# Sheet2.net
KiCad netlist of a schematic drawn in Altium Designer
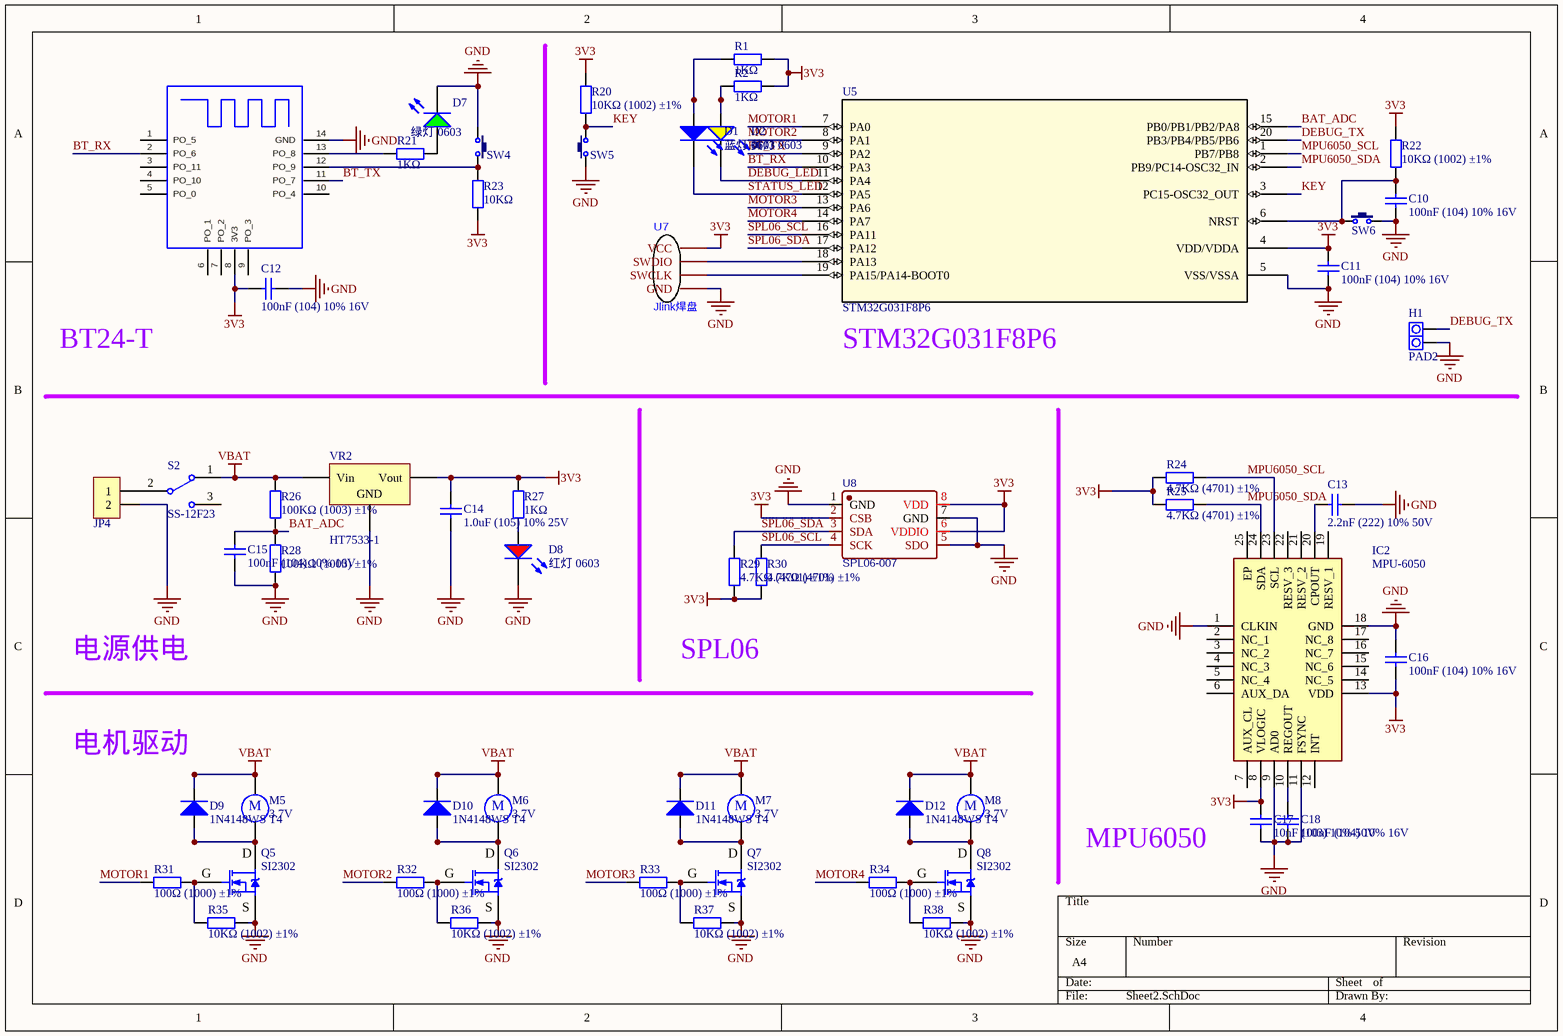
[diagram p0: Sheet2.SchDoc]

(export (version "E")
  (design (tool "Eeschema 10.0.6"))
  (components
    (comp (ref "C10")
      (value "100nF (104) 10% 16V")
      (footprint "0402_C")
      (description "贴片电容")
      (libsource (lib "Cap") (part "0402 100nF (104) 10% 16V"))
    )
    (comp (ref "C11")
      (value "100nF (104) 10% 16V")
      (footprint "0402_C")
      (description "贴片电容")
      (libsource (lib "Cap") (part "0402 100nF (104) 10% 16V"))
    )
    (comp (ref "C12")
      (value "100nF (104) 10% 16V")
      (footprint "0402_C")
      (description "贴片电容")
      (libsource (lib "Cap") (part "0402 100nF (104) 10% 16V"))
    )
    (comp (ref "C13")
      (value "2.2nF (222) 10% 50V")
      (footprint "0402_C")
      (description "贴片电容")
      (libsource (lib "Cap") (part "0402 2.2nF (222) 10% 50V"))
    )
    (comp (ref "C14")
      (value "1.0uF (105) 10% 25V")
      (footprint "0402_C")
      (description "贴片电容")
      (libsource (lib "Cap") (part "0402 1.0uF (105) 10% 25V"))
    )
    (comp (ref "C15")
      (value "100nF (104) 10% 16V")
      (footprint "0402_C")
      (description "贴片电容")
      (libsource (lib "Cap") (part "0402 100nF (104) 10% 16V"))
    )
    (comp (ref "C16")
      (value "100nF (104) 10% 16V")
      (footprint "0402_C")
      (description "贴片电容")
      (libsource (lib "Cap") (part "0402 100nF (104) 10% 16V"))
    )
    (comp (ref "C17")
      (value "10nF (103) 10% 50V")
      (footprint "0402_C")
      (description "贴片电容")
      (libsource (lib "Cap") (part "0402 10nF (103) 10% 50V"))
    )
    (comp (ref "C18")
      (value "100nF (104) 10% 16V")
      (footprint "0402_C")
      (description "贴片电容")
      (libsource (lib "Cap") (part "0402 100nF (104) 10% 16V"))
    )
    (comp (ref "D1")
      (value "蓝灯 0603")
      (footprint "0603_LED_S1")
      (description "发光二极管")
      (libsource (lib "LED") (part "0603 蓝灯"))
    )
    (comp (ref "D2")
      (value "黄灯 0603")
      (footprint "0603_LED_S1")
      (description "发光二极管")
      (libsource (lib "LED") (part "0603 黄灯"))
    )
    (comp (ref "D7")
      (value "绿灯 0603")
      (footprint "0603_LED_S1")
      (description "发光二极管")
      (libsource (lib "LED") (part "0603 绿灯"))
    )
    (comp (ref "D8")
      (value "红灯 0603")
      (footprint "0603_LED_S1")
      (description "发光二极管")
      (libsource (lib "LED") (part "0603 红灯"))
    )
    (comp (ref "D9")
      (value "1N4148WS T4")
      (footprint "SOD-323")
      (description "二极管")
      (libsource (lib "Diode") (part "SOD-323 1N4148WS T4"))
    )
    (comp (ref "D10")
      (value "1N4148WS T4")
      (footprint "SOD-323")
      (description "二极管")
      (libsource (lib "Diode") (part "SOD-323 1N4148WS T4"))
    )
    (comp (ref "D11")
      (value "1N4148WS T4")
      (footprint "SOD-323")
      (description "二极管")
      (libsource (lib "Diode") (part "SOD-323 1N4148WS T4"))
    )
    (comp (ref "D12")
      (value "1N4148WS T4")
      (footprint "SOD-323")
      (description "二极管")
      (libsource (lib "Diode") (part "SOD-323 1N4148WS T4"))
    )
    (comp (ref "H1")
      (value "PAD2")
      (footprint "PAD2-2.54")
      (description "引线焊盘")
      (fields (field (name "版权归属") "源创客"))
      (libsource (lib "15.1 - 未分类器件") (part "PAD2"))
    )
    (comp (ref "IC2")
      (value "MPU-6050")
      (footprint "SamacSys:MPU6050")
      (description "Integrated Circuit")
      (fields (field (name "MOUSER PART NUMBER") "410-MPU-6050"))
      (libsource (lib "*") (part "MPU-6050"))
    )
    (comp (ref "JP4")
      (value "HDR-1X2")
      (footprint "ZH1.5-WI-2P")
      (description "2P接插件")
      (fields (field (name "版权归属") "源创客"))
      (libsource (lib "4.3   - 接插件-脚距1.5") (part "Header 2"))
    )
    (comp (ref "M5")
      (value "3.7V")
      (footprint "MX 1.25-WI-2P")
      (description "直流电机")
      (fields (field (name "版权归属") "源创客"))
      (libsource (lib "15.1 - 未分类器件") (part "MOTOR"))
    )
    (comp (ref "M6")
      (value "3.7V")
      (footprint "MX 1.25-WI-2P")
      (description "直流电机")
      (fields (field (name "版权归属") "源创客"))
      (libsource (lib "15.1 - 未分类器件") (part "MOTOR"))
    )
    (comp (ref "M7")
      (value "3.7V")
      (footprint "MX 1.25-WI-2P")
      (description "直流电机")
      (fields (field (name "版权归属") "源创客"))
      (libsource (lib "15.1 - 未分类器件") (part "MOTOR"))
    )
    (comp (ref "M8")
      (value "3.7V")
      (footprint "MX 1.25-WI-2P")
      (description "直流电机")
      (fields (field (name "版权归属") "源创客"))
      (libsource (lib "15.1 - 未分类器件") (part "MOTOR"))
    )
    (comp (ref "Q5")
      (value "SI2302")
      (footprint "SOT23-3N")
      (description "N沟道场效应管")
      (fields (field (name "版权归属") "源创客"))
      (libsource (lib "6.1   - 场效应管-可控硅") (part "SI2302"))
    )
    (comp (ref "Q6")
      (value "SI2302")
      (footprint "SOT23-3N")
      (description "N沟道场效应管")
      (fields (field (name "版权归属") "源创客"))
      (libsource (lib "6.1   - 场效应管-可控硅") (part "SI2302"))
    )
    (comp (ref "Q7")
      (value "SI2302")
      (footprint "SOT23-3N")
      (description "N沟道场效应管")
      (fields (field (name "版权归属") "源创客"))
      (libsource (lib "6.1   - 场效应管-可控硅") (part "SI2302"))
    )
    (comp (ref "Q8")
      (value "SI2302")
      (footprint "SOT23-3N")
      (description "N沟道场效应管")
      (fields (field (name "版权归属") "源创客"))
      (libsource (lib "6.1   - 场效应管-可控硅") (part "SI2302"))
    )
    (comp (ref "R1")
      (value "1KΩ")
      (footprint "0402_R")
      (description "贴片电阻")
      (libsource (lib "RES") (part "0402 1KΩ (1001) 1%"))
    )
    (comp (ref "R2")
      (value "1KΩ")
      (footprint "0402_R")
      (description "贴片电阻")
      (libsource (lib "") (part "0402 1KΩ (1001) 1%_1"))
    )
    (comp (ref "R20")
      (value "10KΩ (1002) ±1%")
      (footprint "0402_R")
      (description "贴片电阻")
      (libsource (lib "") (part "0402 10KΩ (1002) 1%_2"))
    )
    (comp (ref "R21")
      (value "1KΩ")
      (footprint "0402_R")
      (description "贴片电阻")
      (libsource (lib "RES") (part "0402 1KΩ (1001) 1%"))
    )
    (comp (ref "R22")
      (value "10KΩ (1002) ±1%")
      (footprint "0402_R")
      (description "贴片电阻")
      (libsource (lib "") (part "0402 10KΩ (1002) 1%_1"))
    )
    (comp (ref "R23")
      (value "10KΩ")
      (footprint "0402_R")
      (description "贴片电阻")
      (libsource (lib "") (part "0402 10KΩ (1002) 1%_1"))
    )
    (comp (ref "R24")
      (value "4.7KΩ (4701) ±1%")
      (footprint "0402_R")
      (description "贴片电阻")
      (libsource (lib "") (part "0402 4.7KΩ (4701) 1%_1"))
    )
    (comp (ref "R25")
      (value "4.7KΩ (4701) ±1%")
      (footprint "0402_R")
      (description "贴片电阻")
      (libsource (lib "") (part "0402 4.7KΩ (4701) 1%_1"))
    )
    (comp (ref "R26")
      (value "100KΩ (1003) ±1%")
      (footprint "0402_R")
      (description "贴片电阻")
      (libsource (lib "RES") (part "0402 100KΩ (1003) 1%"))
    )
    (comp (ref "R27")
      (value "1KΩ")
      (footprint "0402_R")
      (description "贴片电阻")
      (libsource (lib "") (part "0402 1KΩ (1001) 1%_2"))
    )
    (comp (ref "R28")
      (value "100KΩ (1003) ±1%")
      (footprint "0402_R")
      (description "贴片电阻")
      (libsource (lib "RES") (part "0402 100KΩ (1003) 1%"))
    )
    (comp (ref "R29")
      (value "4.7KΩ (4701) ±1%")
      (footprint "0402_R")
      (description "贴片电阻")
      (libsource (lib "RES") (part "0402 4.7KΩ (4701) 1%"))
    )
    (comp (ref "R30")
      (value "4.7KΩ (4701) ±1%")
      (footprint "0402_R")
      (description "贴片电阻")
      (libsource (lib "RES") (part "0402 4.7KΩ (4701) 1%"))
    )
    (comp (ref "R31")
      (value "100Ω (1000) ±1%")
      (footprint "0402_R")
      (description "贴片电阻")
      (libsource (lib "RES") (part "0402 100Ω (1000) 1%"))
    )
    (comp (ref "R32")
      (value "100Ω (1000) ±1%")
      (footprint "0402_R")
      (description "贴片电阻")
      (libsource (lib "RES") (part "0402 100Ω (1000) 1%"))
    )
    (comp (ref "R33")
      (value "100Ω (1000) ±1%")
      (footprint "0402_R")
      (description "贴片电阻")
      (libsource (lib "RES") (part "0402 100Ω (1000) 1%"))
    )
    (comp (ref "R34")
      (value "100Ω (1000) ±1%")
      (footprint "0402_R")
      (description "贴片电阻")
      (libsource (lib "RES") (part "0402 100Ω (1000) 1%"))
    )
    (comp (ref "R35")
      (value "10KΩ (1002) ±1%")
      (footprint "0402_R")
      (description "贴片电阻")
      (libsource (lib "RES") (part "0402 10KΩ (1002) 1%"))
    )
    (comp (ref "R36")
      (value "10KΩ (1002) ±1%")
      (footprint "0402_R")
      (description "贴片电阻")
      (libsource (lib "RES") (part "0402 10KΩ (1002) 1%"))
    )
    (comp (ref "R37")
      (value "10KΩ (1002) ±1%")
      (footprint "0402_R")
      (description "贴片电阻")
      (libsource (lib "RES") (part "0402 10KΩ (1002) 1%"))
    )
    (comp (ref "R38")
      (value "10KΩ (1002) ±1%")
      (footprint "0402_R")
      (description "贴片电阻")
      (libsource (lib "RES") (part "0402 10KΩ (1002) 1%"))
    )
    (comp (ref "S2")
      (value "SS-12F23")
      (footprint "MSK-12C01-07")
      (description "1路波动开关")
      (fields (field (name "版权归属") "源创客"))
      (libsource (lib "5.1   - 按键-开关") (part "SSW-1P"))
    )
    (comp (ref "SW4")
      (value "3x6x5")
      (footprint "SW-SMD_4P-L5.1-W5.1-P3.70-LS6.5-TL-2")
      (description "3x6轻触开关")
      (fields (field (name "版权归属") "源创客"))
      (libsource (lib "5.1   - 按键-开关") (part "TSW 3x6"))
    )
    (comp (ref "SW5")
      (value "3x6x5")
      (footprint "SW-SMD_4P-L5.1-W5.1-P3.70-LS6.5-TL-2")
      (description "3x6轻触开关")
      (fields (field (name "版权归属") "源创客"))
      (libsource (lib "") (part "TSW 3x6_1"))
    )
    (comp (ref "SW6")
      (value "3x6x5")
      (footprint "SW-SMD_4P-L5.1-W5.1-P3.70-LS6.5-TL-2")
      (description "3x6轻触开关")
      (fields (field (name "版权归属") "源创客"))
      (libsource (lib "") (part "TSW 3x6_2"))
    )
    (comp (ref "U5")
      (value "STM32G031F8P6")
      (footprint "TSSOP20")
      (description "No Description Available")
      (fields (field (name "COPYRIGHT") "Copyright (C) 2022 Ultra Librarian. All rights reserved."))
      (libsource (lib "STM32G031F8P6") (part "STM32G031F8P6"))
    )
    (comp (ref "U6") (value "BT24T") (footprint "CC2640T") (libsource (lib "BT24-T") (part "BT24T")))
    (comp (ref "U7")
      (value "Jlink焊盘")
      (footprint "jlink焊盘:PCBComponent_1 - duplicate")
      (libsource (lib "jlink焊盘") (part "Jlink焊盘"))
    )
    (comp (ref "U8")
      (value "SPL06-007")
      (footprint "SENSOR-SMD_SPL06-007")
      (fields (field (name "BOM_SUPPLIER PART") "C233787") (field (name "CONTRIBUTOR") "LCSC"))
      (libsource (lib "SPL06") (part "SPL06-007"))
    )
    (comp (ref "VR2")
      (value "HT7533-1")
      (footprint "SOT-89(SOT-89-3)")
      (description "低压差线性稳压(LDO)")
      (libsource (lib "LDO") (part "SOT-89 HT7533-1"))
    )
  )
  (nets
    (net (code "1") (name "/BAT_ADC") (class "Default")
      (node (ref "C15") (pin "2") (pinfunction "2_2") (pintype "passive"))
      (node (ref "R26") (pin "1") (pinfunction "1_1") (pintype "passive"))
      (node (ref "R28") (pin "2") (pinfunction "2_2") (pintype "passive"))
      (node (ref "U5") (pin "15") (pinfunction "PB0/PB1/PB2/PA8_15") (pintype "bidirectional"))
    )
    (net (code "2") (name "/BT_RX") (class "Default")
      (node (ref "U5") (pin "10") (pinfunction "PA3_10") (pintype "bidirectional"))
      (node (ref "U6") (pin "2") (pinfunction "PO_6_2") (pintype "passive"))
    )
    (net (code "3") (name "/BT_TX") (class "Default")
      (node (ref "U5") (pin "9") (pinfunction "PA2_9") (pintype "bidirectional"))
      (node (ref "U6") (pin "11") (pinfunction "PO_7_11") (pintype "passive"))
    )
    (net (code "4") (name "/DEBUG_LED") (class "Default")
      (node (ref "D2") (pin "K") (pinfunction "K_K") (pintype "passive"))
      (node (ref "U5") (pin "11") (pinfunction "PA4_11") (pintype "bidirectional"))
    )
    (net (code "5") (name "/DEBUG_TX") (class "Default")
      (node (ref "H1") (pin "2") (pinfunction "2_2") (pintype "passive"))
      (node (ref "U5") (pin "20") (pinfunction "PB3/PB4/PB5/PB6_20") (pintype "bidirectional"))
    )
    (net (code "6") (name "/KEY") (class "Default")
      (node (ref "R20") (pin "1") (pinfunction "1_1") (pintype "passive"))
      (node (ref "SW5") (pin "2") (pinfunction "2_2") (pintype "passive"))
      (node (ref "U5") (pin "3") (pinfunction "PC15-OSC32_OUT_3") (pintype "bidirectional"))
    )
    (net (code "7") (name "/MOTOR1") (class "Default")
      (node (ref "R31") (pin "1") (pinfunction "1_1") (pintype "passive"))
      (node (ref "U5") (pin "7") (pinfunction "PA0_7") (pintype "bidirectional"))
    )
    (net (code "8") (name "/MOTOR2") (class "Default")
      (node (ref "R32") (pin "1") (pinfunction "1_1") (pintype "passive"))
      (node (ref "U5") (pin "8") (pinfunction "PA1_8") (pintype "bidirectional"))
    )
    (net (code "9") (name "/MOTOR3") (class "Default")
      (node (ref "R33") (pin "1") (pinfunction "1_1") (pintype "passive"))
      (node (ref "U5") (pin "13") (pinfunction "PA6_13") (pintype "bidirectional"))
    )
    (net (code "10") (name "/MOTOR4") (class "Default")
      (node (ref "R34") (pin "1") (pinfunction "1_1") (pintype "passive"))
      (node (ref "U5") (pin "14") (pinfunction "PA7_14") (pintype "bidirectional"))
    )
    (net (code "11") (name "/MPU6050_SCL") (class "Default")
      (node (ref "IC2") (pin "23") (pinfunction "SCL_23") (pintype "passive"))
      (node (ref "R24") (pin "2") (pinfunction "2_2") (pintype "passive"))
      (node (ref "U5") (pin "1") (pinfunction "PB7/PB8_1") (pintype "bidirectional"))
    )
    (net (code "12") (name "/MPU6050_SDA") (class "Default")
      (node (ref "IC2") (pin "24") (pinfunction "SDA_24") (pintype "passive"))
      (node (ref "R25") (pin "2") (pinfunction "2_2") (pintype "passive"))
      (node (ref "U5") (pin "2") (pinfunction "PB9/PC14-OSC32_IN_2") (pintype "bidirectional"))
    )
    (net (code "13") (name "/SPL06_SCL") (class "Default")
      (node (ref "R30") (pin "2") (pinfunction "2_2") (pintype "passive"))
      (node (ref "U5") (pin "16") (pinfunction "PA11_16") (pintype "bidirectional"))
      (node (ref "U8") (pin "4") (pinfunction "SCK_4") (pintype "passive"))
    )
    (net (code "14") (name "/SPL06_SDA") (class "Default")
      (node (ref "R29") (pin "2") (pinfunction "2_2") (pintype "passive"))
      (node (ref "U5") (pin "17") (pinfunction "PA12_17") (pintype "bidirectional"))
      (node (ref "U8") (pin "3") (pinfunction "SDA_3") (pintype "passive"))
    )
    (net (code "15") (name "/STATUS_LED") (class "Default")
      (node (ref "D1") (pin "K") (pinfunction "K_K") (pintype "passive"))
      (node (ref "U5") (pin "12") (pinfunction "PA5_12") (pintype "bidirectional"))
    )
    (net (code "16") (name "3V3") (class "Default")
      (node (ref "C11") (pin "1") (pinfunction "1_1") (pintype "passive"))
      (node (ref "C12") (pin "2") (pinfunction "2_2") (pintype "passive"))
      (node (ref "C14") (pin "2") (pinfunction "2_2") (pintype "passive"))
      (node (ref "C16") (pin "1") (pinfunction "1_1") (pintype "passive"))
      (node (ref "C17") (pin "2") (pinfunction "2_2") (pintype "passive"))
      (node (ref "IC2") (pin "13") (pinfunction "VDD_13") (pintype "passive"))
      (node (ref "IC2") (pin "8") (pinfunction "VLOGIC_8") (pintype "passive"))
      (node (ref "R1") (pin "2") (pinfunction "2_2") (pintype "passive"))
      (node (ref "R2") (pin "1") (pinfunction "1_1") (pintype "passive"))
      (node (ref "R20") (pin "2") (pinfunction "2_2") (pintype "passive"))
      (node (ref "R22") (pin "1") (pinfunction "1_1") (pintype "passive"))
      (node (ref "R23") (pin "2") (pinfunction "2_2") (pintype "passive"))
      (node (ref "R24") (pin "1") (pinfunction "1_1") (pintype "passive"))
      (node (ref "R25") (pin "1") (pinfunction "1_1") (pintype "passive"))
      (node (ref "R27") (pin "2") (pinfunction "2_2") (pintype "passive"))
      (node (ref "R29") (pin "1") (pinfunction "1_1") (pintype "passive"))
      (node (ref "R30") (pin "1") (pinfunction "1_1") (pintype "passive"))
      (node (ref "U5") (pin "4") (pinfunction "VDD/VDDA_4") (pintype "power_in"))
      (node (ref "U6") (pin "8") (pinfunction "3V3_8") (pintype "passive"))
      (node (ref "U7") (pin "1") (pinfunction "VCC_1") (pintype "passive"))
      (node (ref "U8") (pin "2") (pinfunction "CSB_2") (pintype "passive"))
      (node (ref "U8") (pin "6") (pinfunction "VDDIO_6") (pintype "passive"))
      (node (ref "U8") (pin "8") (pinfunction "VDD_8") (pintype "passive"))
      (node (ref "VR2") (pin "3") (pinfunction "Vout_3") (pintype "passive"))
    )
    (net (code "17") (name "GND") (class "Default")
      (node (ref "C10") (pin "2") (pinfunction "2_2") (pintype "passive"))
      (node (ref "C11") (pin "2") (pinfunction "2_2") (pintype "passive"))
      (node (ref "C12") (pin "1") (pinfunction "1_1") (pintype "passive"))
      (node (ref "C13") (pin "2") (pinfunction "2_2") (pintype "passive"))
      (node (ref "C14") (pin "1") (pinfunction "1_1") (pintype "passive"))
      (node (ref "C15") (pin "1") (pinfunction "1_1") (pintype "passive"))
      (node (ref "C16") (pin "2") (pinfunction "2_2") (pintype "passive"))
      (node (ref "C17") (pin "1") (pinfunction "1_1") (pintype "passive"))
      (node (ref "C18") (pin "1") (pinfunction "1_1") (pintype "passive"))
      (node (ref "D7") (pin "K") (pinfunction "K_K") (pintype "passive"))
      (node (ref "D8") (pin "K") (pinfunction "K_K") (pintype "passive"))
      (node (ref "H1") (pin "1") (pinfunction "1_1") (pintype "passive"))
      (node (ref "IC2") (pin "1") (pinfunction "CLKIN_1") (pintype "passive"))
      (node (ref "IC2") (pin "11") (pinfunction "FSYNC_11") (pintype "passive"))
      (node (ref "IC2") (pin "18") (pinfunction "GND_18") (pintype "passive"))
      (node (ref "IC2") (pin "9") (pinfunction "AD0_9") (pintype "passive"))
      (node (ref "JP4") (pin "2") (pinfunction "2_2") (pintype "passive"))
      (node (ref "Q5") (pin "2") (pinfunction "S_2") (pintype "passive"))
      (node (ref "Q6") (pin "2") (pinfunction "S_2") (pintype "passive"))
      (node (ref "Q7") (pin "2") (pinfunction "S_2") (pintype "passive"))
      (node (ref "Q8") (pin "2") (pinfunction "S_2") (pintype "passive"))
      (node (ref "R28") (pin "1") (pinfunction "1_1") (pintype "passive"))
      (node (ref "R35") (pin "2") (pinfunction "2_2") (pintype "passive"))
      (node (ref "R36") (pin "2") (pinfunction "2_2") (pintype "passive"))
      (node (ref "R37") (pin "2") (pinfunction "2_2") (pintype "passive"))
      (node (ref "R38") (pin "2") (pinfunction "2_2") (pintype "passive"))
      (node (ref "SW4") (pin "1") (pinfunction "1_1") (pintype "passive"))
      (node (ref "SW5") (pin "1") (pinfunction "1_1") (pintype "passive"))
      (node (ref "SW6") (pin "2") (pinfunction "2_2") (pintype "passive"))
      (node (ref "U5") (pin "5") (pinfunction "VSS/VSSA_5") (pintype "power_in"))
      (node (ref "U6") (pin "14") (pinfunction "GND_14") (pintype "passive"))
      (node (ref "U7") (pin "4") (pinfunction "GND_4") (pintype "passive"))
      (node (ref "U8") (pin "1") (pinfunction "GND_1") (pintype "passive"))
      (node (ref "U8") (pin "5") (pinfunction "SDO_5") (pintype "passive"))
      (node (ref "U8") (pin "7") (pinfunction "GND_7") (pintype "passive"))
      (node (ref "VR2") (pin "1") (pinfunction "GND_1") (pintype "passive"))
    )
    (net (code "18") (name "Net-(D1-PadA)") (class "Default")
      (node (ref "D1") (pin "A") (pinfunction "A_A") (pintype "passive"))
      (node (ref "R1") (pin "1") (pinfunction "1_1") (pintype "passive"))
    )
    (net (code "19") (name "Net-(D2-PadA)") (class "Default")
      (node (ref "D2") (pin "A") (pinfunction "A_A") (pintype "passive"))
      (node (ref "R2") (pin "2") (pinfunction "2_2") (pintype "passive"))
    )
    (net (code "20") (name "Net-(D7-PadA)") (class "Default")
      (node (ref "D7") (pin "A") (pinfunction "A_A") (pintype "passive"))
      (node (ref "R21") (pin "2") (pinfunction "2_2") (pintype "passive"))
    )
    (net (code "21") (name "Net-(D8-PadA)") (class "Default")
      (node (ref "D8") (pin "A") (pinfunction "A_A") (pintype "passive"))
      (node (ref "R27") (pin "1") (pinfunction "1_1") (pintype "passive"))
    )
    (net (code "22") (name "Net-(D9-A)") (class "Default")
      (node (ref "D9") (pin "1") (pinfunction "A_1") (pintype "passive"))
      (node (ref "M5") (pin "2") (pinfunction "2_2") (pintype "passive"))
      (node (ref "Q5") (pin "3") (pinfunction "D_3") (pintype "passive"))
    )
    (net (code "23") (name "Net-(D10-A)") (class "Default")
      (node (ref "D10") (pin "1") (pinfunction "A_1") (pintype "passive"))
      (node (ref "M6") (pin "2") (pinfunction "2_2") (pintype "passive"))
      (node (ref "Q6") (pin "3") (pinfunction "D_3") (pintype "passive"))
    )
    (net (code "24") (name "Net-(D11-A)") (class "Default")
      (node (ref "D11") (pin "1") (pinfunction "A_1") (pintype "passive"))
      (node (ref "M7") (pin "2") (pinfunction "2_2") (pintype "passive"))
      (node (ref "Q7") (pin "3") (pinfunction "D_3") (pintype "passive"))
    )
    (net (code "25") (name "Net-(D12-A)") (class "Default")
      (node (ref "D12") (pin "1") (pinfunction "A_1") (pintype "passive"))
      (node (ref "M8") (pin "2") (pinfunction "2_2") (pintype "passive"))
      (node (ref "Q8") (pin "3") (pinfunction "D_3") (pintype "passive"))
    )
    (net (code "26") (name "Net-(IC2-CPOUT)") (class "Default")
      (node (ref "C13") (pin "1") (pinfunction "1_1") (pintype "passive"))
      (node (ref "IC2") (pin "20") (pinfunction "CPOUT_20") (pintype "passive"))
    )
    (net (code "27") (name "Net-(IC2-REGOUT)") (class "Default")
      (node (ref "C18") (pin "2") (pinfunction "2_2") (pintype "passive"))
      (node (ref "IC2") (pin "10") (pinfunction "REGOUT_10") (pintype "passive"))
    )
    (net (code "28") (name "Net-(JP4-Pad1)") (class "Default")
      (node (ref "JP4") (pin "1") (pinfunction "1_1") (pintype "passive"))
      (node (ref "S2") (pin "2") (pinfunction "2_2") (pintype "passive"))
    )
    (net (code "29") (name "Net-(Q5-G)") (class "Default")
      (node (ref "Q5") (pin "1") (pinfunction "G_1") (pintype "passive"))
      (node (ref "R31") (pin "2") (pinfunction "2_2") (pintype "passive"))
      (node (ref "R35") (pin "1") (pinfunction "1_1") (pintype "passive"))
    )
    (net (code "30") (name "Net-(Q6-G)") (class "Default")
      (node (ref "Q6") (pin "1") (pinfunction "G_1") (pintype "passive"))
      (node (ref "R32") (pin "2") (pinfunction "2_2") (pintype "passive"))
      (node (ref "R36") (pin "1") (pinfunction "1_1") (pintype "passive"))
    )
    (net (code "31") (name "Net-(Q7-G)") (class "Default")
      (node (ref "Q7") (pin "1") (pinfunction "G_1") (pintype "passive"))
      (node (ref "R33") (pin "2") (pinfunction "2_2") (pintype "passive"))
      (node (ref "R37") (pin "1") (pinfunction "1_1") (pintype "passive"))
    )
    (net (code "32") (name "Net-(Q8-G)") (class "Default")
      (node (ref "Q8") (pin "1") (pinfunction "G_1") (pintype "passive"))
      (node (ref "R34") (pin "2") (pinfunction "2_2") (pintype "passive"))
      (node (ref "R38") (pin "1") (pinfunction "1_1") (pintype "passive"))
    )
    (net (code "33") (name "Net-(U5-NRST)") (class "Default")
      (node (ref "C10") (pin "1") (pinfunction "1_1") (pintype "passive"))
      (node (ref "R22") (pin "2") (pinfunction "2_2") (pintype "passive"))
      (node (ref "SW6") (pin "1") (pinfunction "1_1") (pintype "passive"))
      (node (ref "U5") (pin "6") (pinfunction "NRST_6") (pintype "bidirectional"))
    )
    (net (code "34") (name "Net-(U5-PA13)") (class "Default")
      (node (ref "U5") (pin "18") (pinfunction "PA13_18") (pintype "bidirectional"))
      (node (ref "U7") (pin "2") (pinfunction "SWDIO_2") (pintype "passive"))
    )
    (net (code "35") (name "Net-(U5-PA15{slash}PA14-BOOT0)") (class "Default")
      (node (ref "U5") (pin "19") (pinfunction "PA15/PA14-BOOT0_19") (pintype "bidirectional"))
      (node (ref "U7") (pin "3") (pinfunction "SWCLK_3") (pintype "passive"))
    )
    (net (code "36") (name "Net-(U6-PO_8)") (class "Default")
      (node (ref "R21") (pin "1") (pinfunction "1_1") (pintype "passive"))
      (node (ref "U6") (pin "13") (pinfunction "PO_8_13") (pintype "passive"))
    )
    (net (code "37") (name "Net-(U6-PO_9)") (class "Default")
      (node (ref "R23") (pin "1") (pinfunction "1_1") (pintype "passive"))
      (node (ref "SW4") (pin "2") (pinfunction "2_2") (pintype "passive"))
      (node (ref "U6") (pin "12") (pinfunction "PO_9_12") (pintype "passive"))
    )
    (net (code "38") (name "VBAT") (class "Default")
      (node (ref "D10") (pin "2") (pinfunction "K_2") (pintype "passive"))
      (node (ref "D11") (pin "2") (pinfunction "K_2") (pintype "passive"))
      (node (ref "D12") (pin "2") (pinfunction "K_2") (pintype "passive"))
      (node (ref "D9") (pin "2") (pinfunction "K_2") (pintype "passive"))
      (node (ref "M5") (pin "1") (pinfunction "1_1") (pintype "passive"))
      (node (ref "M6") (pin "1") (pinfunction "1_1") (pintype "passive"))
      (node (ref "M7") (pin "1") (pinfunction "1_1") (pintype "passive"))
      (node (ref "M8") (pin "1") (pinfunction "1_1") (pintype "passive"))
      (node (ref "R26") (pin "2") (pinfunction "2_2") (pintype "passive"))
      (node (ref "S2") (pin "1") (pinfunction "1_1") (pintype "passive"))
      (node (ref "VR2") (pin "2") (pinfunction "Vin_2") (pintype "passive"))
    )
    (net (code "39") (name "unconnected-(IC2-AUX_CL-Pad7)") (class "Default")
      (node (ref "IC2") (pin "7") (pinfunction "AUX_CL_7") (pintype "passive"))
    )
    (net (code "40") (name "unconnected-(IC2-AUX_DA-Pad6)") (class "Default")
      (node (ref "IC2") (pin "6") (pinfunction "AUX_DA_6") (pintype "passive"))
    )
    (net (code "41") (name "unconnected-(IC2-EP-Pad25)") (class "Default")
      (node (ref "IC2") (pin "25") (pinfunction "EP_25") (pintype "passive"))
    )
    (net (code "42") (name "unconnected-(IC2-INT-Pad12)") (class "Default")
      (node (ref "IC2") (pin "12") (pinfunction "INT_12") (pintype "passive"))
    )
    (net (code "43") (name "unconnected-(IC2-NC_1-Pad2)") (class "Default")
      (node (ref "IC2") (pin "2") (pinfunction "NC_1_2") (pintype "passive"))
    )
    (net (code "44") (name "unconnected-(IC2-NC_2-Pad3)") (class "Default")
      (node (ref "IC2") (pin "3") (pinfunction "NC_2_3") (pintype "passive"))
    )
    (net (code "45") (name "unconnected-(IC2-NC_3-Pad4)") (class "Default")
      (node (ref "IC2") (pin "4") (pinfunction "NC_3_4") (pintype "passive"))
    )
    (net (code "46") (name "unconnected-(IC2-NC_4-Pad5)") (class "Default")
      (node (ref "IC2") (pin "5") (pinfunction "NC_4_5") (pintype "passive"))
    )
    (net (code "47") (name "unconnected-(IC2-NC_5-Pad14)") (class "Default")
      (node (ref "IC2") (pin "14") (pinfunction "NC_5_14") (pintype "passive"))
    )
    (net (code "48") (name "unconnected-(IC2-NC_6-Pad15)") (class "Default")
      (node (ref "IC2") (pin "15") (pinfunction "NC_6_15") (pintype "passive"))
    )
    (net (code "49") (name "unconnected-(IC2-NC_7-Pad16)") (class "Default")
      (node (ref "IC2") (pin "16") (pinfunction "NC_7_16") (pintype "passive"))
    )
    (net (code "50") (name "unconnected-(IC2-NC_8-Pad17)") (class "Default")
      (node (ref "IC2") (pin "17") (pinfunction "NC_8_17") (pintype "passive"))
    )
    (net (code "51") (name "unconnected-(IC2-RESV_1-Pad19)") (class "Default")
      (node (ref "IC2") (pin "19") (pinfunction "RESV_1_19") (pintype "passive"))
    )
    (net (code "52") (name "unconnected-(IC2-RESV_2-Pad21)") (class "Default")
      (node (ref "IC2") (pin "21") (pinfunction "RESV_2_21") (pintype "passive"))
    )
    (net (code "53") (name "unconnected-(IC2-RESV_3-Pad22)") (class "Default")
      (node (ref "IC2") (pin "22") (pinfunction "RESV_3_22") (pintype "passive"))
    )
    (net (code "54") (name "unconnected-(S2-Pad3)") (class "Default")
      (node (ref "S2") (pin "3") (pinfunction "3_3") (pintype "passive"))
    )
    (net (code "55") (name "unconnected-(U6-PO_0-Pad5)") (class "Default")
      (node (ref "U6") (pin "5") (pinfunction "PO_0_5") (pintype "passive"))
    )
    (net (code "56") (name "unconnected-(U6-PO_1-Pad6)") (class "Default")
      (node (ref "U6") (pin "6") (pinfunction "PO_1_6") (pintype "passive"))
    )
    (net (code "57") (name "unconnected-(U6-PO_2-Pad7)") (class "Default")
      (node (ref "U6") (pin "7") (pinfunction "PO_2_7") (pintype "passive"))
    )
    (net (code "58") (name "unconnected-(U6-PO_3-Pad9)") (class "Default")
      (node (ref "U6") (pin "9") (pinfunction "PO_3_9") (pintype "passive"))
    )
    (net (code "59") (name "unconnected-(U6-PO_4-Pad10)") (class "Default")
      (node (ref "U6") (pin "10") (pinfunction "PO_4_10") (pintype "passive"))
    )
    (net (code "60") (name "unconnected-(U6-PO_5-Pad1)") (class "Default")
      (node (ref "U6") (pin "1") (pinfunction "PO_5_1") (pintype "passive"))
    )
    (net (code "61") (name "unconnected-(U6-PO_10-Pad4)") (class "Default")
      (node (ref "U6") (pin "4") (pinfunction "PO_10_4") (pintype "passive"))
    )
    (net (code "62") (name "unconnected-(U6-PO_11-Pad3)") (class "Default")
      (node (ref "U6") (pin "3") (pinfunction "PO_11_3") (pintype "passive"))
    )
  )
)
